# TB_Microcontroller.net
KiCad netlist of a schematic drawn in Altium Designer
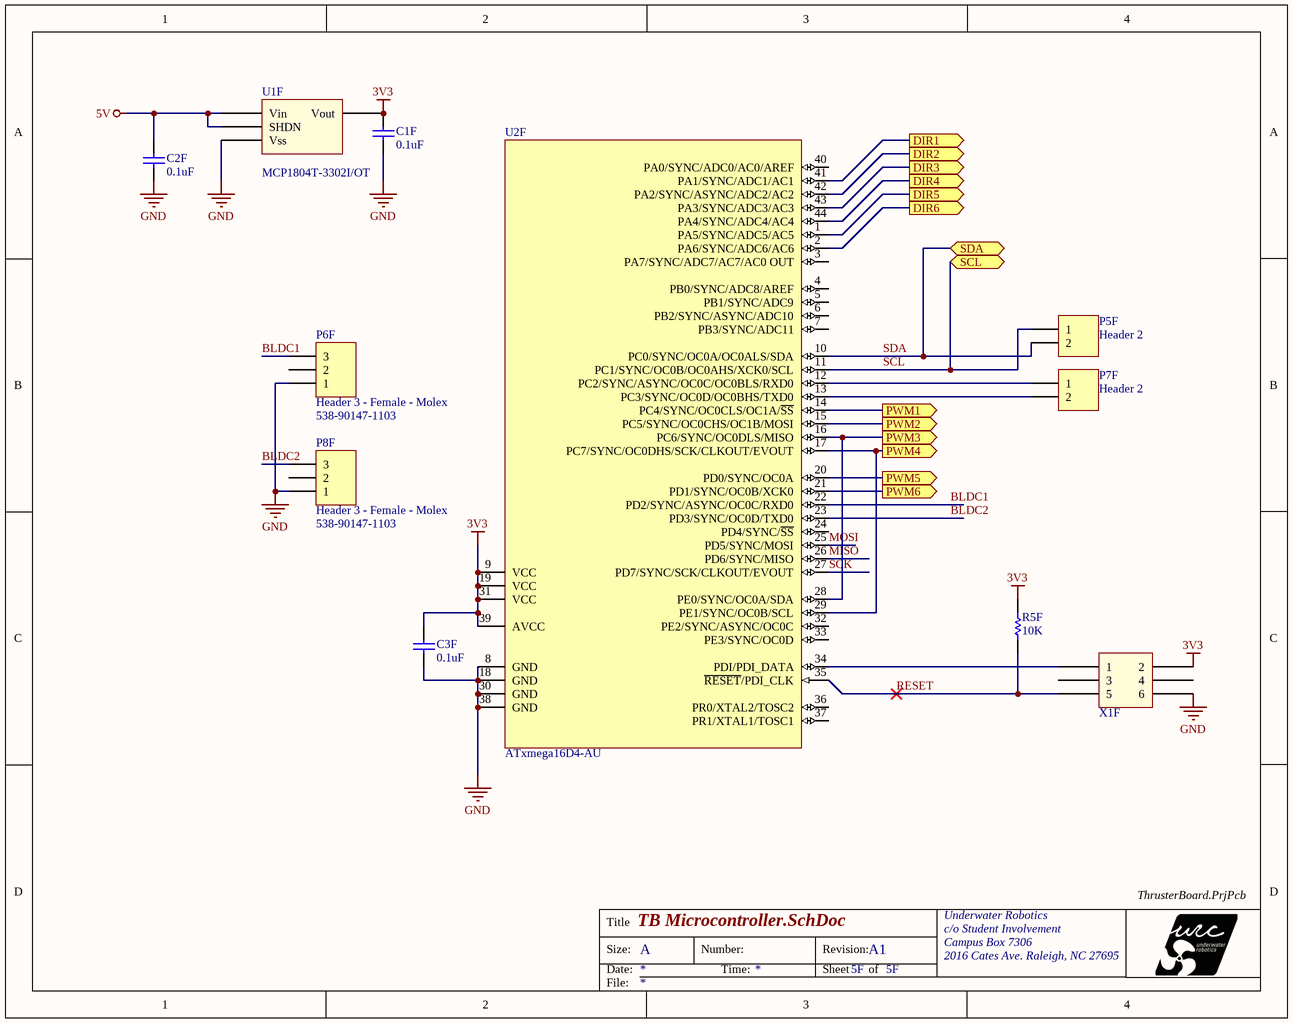
[diagram p0: TB Microcontroller.SchDoc]

(export (version "E")
  (design (tool "Eeschema 10.0.6"))
  (components
    (comp (ref "C1F")
      (value "0.1uF")
      (footprint "C0603")
      (description "Ceramic MLCC, Multicompo, X7R Dielectric")
      (fields
        (field (name "MANUFACTURER PART NUMBER") "MC0603B104K500CT")
        (field (name "Comment") "0.1uF, C0603, MultiComp")
      )
      (libsource (lib "Capacitors SchLib") (part "0.1uF, C0603, MultiComp"))
    )
    (comp (ref "C2F")
      (value "0.1uF")
      (footprint "C0603")
      (description "Ceramic MLCC, Multicompo, X7R Dielectric")
      (fields
        (field (name "MANUFACTURER PART NUMBER") "MC0603B104K500CT")
        (field (name "Comment") "0.1uF, C0603, MultiComp")
      )
      (libsource (lib "Capacitors SchLib") (part "0.1uF, C0603, MultiComp"))
    )
    (comp (ref "C3F")
      (value "0.1uF")
      (footprint "C0603")
      (description "Ceramic MLCC, Multicompo, X7R Dielectric")
      (fields
        (field (name "MANUFACTURER PART NUMBER") "MC0603B104K500CT")
        (field (name "Comment") "0.1uF, C0603, MultiComp")
      )
      (libsource (lib "Capacitors SchLib") (part "0.1uF, C0603, MultiComp"))
    )
    (comp (ref "P5F")
      (value "Header 2")
      (footprint "HDR1X2")
      (description "Header, 2-Pin")
      (fields (field (name "PUBLISHER") "Altium Limited"))
      (libsource (lib "Miscellaneous Connectors") (part "Header 2"))
    )
    (comp (ref "P6F")
      (value "Header 3 - Female - Molex")
      (footprint "HDR1X3 - Female - Molex")
      (description "Header, 3-Pin")
      (fields
        (field (name "MANUFACTURER") "Molex")
        (field (name "MANUFACTURER PART NUMBER") "90147-1103")
        (field (name "SUPPLIER PART NUMBER 1") "538-90147-1103")
      )
      (libsource (lib "URC_Lib") (part "Header 3 - Female - Molex"))
    )
    (comp (ref "P7F")
      (value "Header 2")
      (footprint "HDR1X2")
      (description "Header, 2-Pin")
      (fields (field (name "PUBLISHER") "Altium Limited"))
      (libsource (lib "Miscellaneous Connectors") (part "Header 2"))
    )
    (comp (ref "P8F")
      (value "Header 3 - Female - Molex")
      (footprint "HDR1X3 - Female - Molex")
      (description "Header, 3-Pin")
      (fields
        (field (name "MANUFACTURER") "Molex")
        (field (name "MANUFACTURER PART NUMBER") "90147-1103")
        (field (name "SUPPLIER PART NUMBER 1") "538-90147-1103")
      )
      (libsource (lib "URC_Lib") (part "Header 3 - Female - Molex"))
    )
    (comp (ref "R5F")
      (value "10K")
      (footprint "R0603")
      (description "Resistor")
      (fields (field (name "TOLERANCE") "1%") (field (name "MANUFACTURER PART NUMBER") "RC0603FR-1010KL"))
      (libsource (lib "Resistors SchLib") (part "10k, 1%, 100mW, Yageo, R0603"))
    )
    (comp (ref "U1F")
      (value "MCP1804T-3302I/OT")
      (footprint "MCP1804T-3302I/OT")
      (description "3.3V Linear Regulator")
      (fields (field (name "MANUFACTURER PART NUMBER") "MCP1804T-3302I/OT"))
      (libsource (lib "URC") (part "MCP1804T-3302I/OT"))
    )
    (comp (ref "U2F")
      (value "ATxmega16D4-AU")
      (footprint "44A_N")
      (fields (field (name "MANUFACTURER PART NUMBER") "ATXMEGA16D4-AU"))
      (libsource (lib "Atmel Microcontroller AVR XMEGA") (part "ATxmega16D4-AU"))
    )
    (comp (ref "X1F")
      (value "Header")
      (footprint "2x3 Header")
      (description "2x3 Header")
      (fields (field (name "MANUFACTURER PART NUMBER") "67996-406HLF"))
      (libsource (lib "URC") (part "2x3 Header"))
    )
  )
  (nets
    (net (code "1") (name "/BLDC1") (class "Default")
      (node (ref "P6F") (pin "3") (pinfunction "3_3") (pintype "passive"))
      (node (ref "U2F") (pin "22") (pinfunction "PD2/SYNC/ASYNC/OC0C/RXD0_22") (pintype "bidirectional"))
    )
    (net (code "2") (name "/BLDC2") (class "Default")
      (node (ref "P8F") (pin "3") (pinfunction "3_3") (pintype "passive"))
      (node (ref "U2F") (pin "23") (pinfunction "PD3/SYNC/OC0D/TXD0_23") (pintype "bidirectional"))
    )
    (net (code "3") (name "/DIR1") (class "Default")
      (node (ref "U2F") (pin "41") (pinfunction "PA1/SYNC/ADC1/AC1_41") (pintype "bidirectional"))
    )
    (net (code "4") (name "/DIR2") (class "Default")
      (node (ref "U2F") (pin "42") (pinfunction "PA2/SYNC/ASYNC/ADC2/AC2_42") (pintype "bidirectional"))
    )
    (net (code "5") (name "/DIR3") (class "Default")
      (node (ref "U2F") (pin "43") (pinfunction "PA3/SYNC/ADC3/AC3_43") (pintype "bidirectional"))
    )
    (net (code "6") (name "/DIR4") (class "Default")
      (node (ref "U2F") (pin "44") (pinfunction "PA4/SYNC/ADC4/AC4_44") (pintype "bidirectional"))
    )
    (net (code "7") (name "/DIR5") (class "Default")
      (node (ref "U2F") (pin "1") (pinfunction "PA5/SYNC/ADC5/AC5_1") (pintype "bidirectional"))
    )
    (net (code "8") (name "/DIR6") (class "Default")
      (node (ref "U2F") (pin "2") (pinfunction "PA6/SYNC/ADC6/AC6_2") (pintype "bidirectional"))
    )
    (net (code "9") (name "/MISO") (class "Default")
      (node (ref "U2F") (pin "26") (pinfunction "PD6/SYNC/MISO_26") (pintype "bidirectional"))
    )
    (net (code "10") (name "/MOSI") (class "Default")
      (node (ref "U2F") (pin "25") (pinfunction "PD5/SYNC/MOSI_25") (pintype "bidirectional"))
    )
    (net (code "11") (name "/PWM1") (class "Default")
      (node (ref "U2F") (pin "14") (pinfunction "PC4/SYNC/OC0CLS/OC1A/~{SS}_14") (pintype "bidirectional"))
    )
    (net (code "12") (name "/PWM2") (class "Default")
      (node (ref "U2F") (pin "15") (pinfunction "PC5/SYNC/OC0CHS/OC1B/MOSI_15") (pintype "bidirectional"))
    )
    (net (code "13") (name "/PWM3") (class "Default")
      (node (ref "U2F") (pin "16") (pinfunction "PC6/SYNC/OC0DLS/MISO_16") (pintype "bidirectional"))
      (node (ref "U2F") (pin "28") (pinfunction "PE0/SYNC/OC0A/SDA_28") (pintype "bidirectional"))
    )
    (net (code "14") (name "/PWM4") (class "Default")
      (node (ref "U2F") (pin "17") (pinfunction "PC7/SYNC/OC0DHS/SCK/CLKOUT/EVOUT_17") (pintype "bidirectional"))
      (node (ref "U2F") (pin "29") (pinfunction "PE1/SYNC/OC0B/SCL_29") (pintype "bidirectional"))
    )
    (net (code "15") (name "/PWM5") (class "Default")
      (node (ref "U2F") (pin "20") (pinfunction "PD0/SYNC/OC0A_20") (pintype "bidirectional"))
    )
    (net (code "16") (name "/PWM6") (class "Default")
      (node (ref "U2F") (pin "21") (pinfunction "PD1/SYNC/OC0B/XCK0_21") (pintype "bidirectional"))
    )
    (net (code "18") (name "/RESET") (class "Default")
      (node (ref "R5F") (pin "1") (pinfunction "1_1") (pintype "passive"))
      (node (ref "U2F") (pin "35") (pinfunction "~{RESET}/PDI_CLK_35") (pintype "input"))
      (node (ref "X1F") (pin "5") (pinfunction "5_5") (pintype "passive"))
    )
    (net (code "19") (name "/SCK") (class "Default")
      (node (ref "U2F") (pin "27") (pinfunction "PD7/SYNC/SCK/CLKOUT/EVOUT_27") (pintype "bidirectional"))
    )
    (net (code "20") (name "/SCL") (class "Default")
      (node (ref "P5F") (pin "1") (pinfunction "1_1") (pintype "passive"))
      (node (ref "U2F") (pin "11") (pinfunction "PC1/SYNC/OC0B/OC0AHS/XCK0/SCL_11") (pintype "bidirectional"))
    )
    (net (code "21") (name "/SDA") (class "Default")
      (node (ref "P5F") (pin "2") (pinfunction "2_2") (pintype "passive"))
      (node (ref "U2F") (pin "10") (pinfunction "PC0/SYNC/OC0A/OC0ALS/SDA_10") (pintype "bidirectional"))
    )
    (net (code "22") (name "3V3") (class "Default")
      (node (ref "C1F") (pin "1") (pinfunction "+_1") (pintype "passive"))
      (node (ref "C3F") (pin "1") (pinfunction "+_1") (pintype "passive"))
      (node (ref "R5F") (pin "2") (pinfunction "2_2") (pintype "passive"))
      (node (ref "U1F") (pin "Vout") (pinfunction "Vout_Vout") (pintype "passive"))
      (node (ref "U2F") (pin "19") (pinfunction "VCC_19") (pintype "power_in"))
      (node (ref "U2F") (pin "31") (pinfunction "VCC_31") (pintype "power_in"))
      (node (ref "U2F") (pin "39") (pinfunction "AVCC_39") (pintype "power_in"))
      (node (ref "U2F") (pin "9") (pinfunction "VCC_9") (pintype "power_in"))
      (node (ref "X1F") (pin "2") (pinfunction "2_2") (pintype "passive"))
    )
    (net (code "23") (name "5V") (class "Default")
      (node (ref "C2F") (pin "1") (pinfunction "+_1") (pintype "passive"))
      (node (ref "U1F") (pin "SHDN") (pinfunction "SHDN_SHDN") (pintype "passive"))
      (node (ref "U1F") (pin "Vin") (pinfunction "Vin_Vin") (pintype "passive"))
    )
    (net (code "24") (name "GND") (class "Default")
      (node (ref "C1F") (pin "2") (pinfunction "2_2") (pintype "passive"))
      (node (ref "C2F") (pin "2") (pinfunction "2_2") (pintype "passive"))
      (node (ref "C3F") (pin "2") (pinfunction "2_2") (pintype "passive"))
      (node (ref "P6F") (pin "1") (pinfunction "1_1") (pintype "passive"))
      (node (ref "P8F") (pin "1") (pinfunction "1_1") (pintype "passive"))
      (node (ref "U1F") (pin "Vss") (pinfunction "Vss_Vss") (pintype "passive"))
      (node (ref "U2F") (pin "18") (pinfunction "GND_18") (pintype "power_in"))
      (node (ref "U2F") (pin "30") (pinfunction "GND_30") (pintype "power_in"))
      (node (ref "U2F") (pin "38") (pinfunction "GND_38") (pintype "power_in"))
      (node (ref "U2F") (pin "8") (pinfunction "GND_8") (pintype "power_in"))
      (node (ref "X1F") (pin "6") (pinfunction "6_6") (pintype "passive"))
    )
    (net (code "25") (name "Net-(U2F-PC2{slash}SYNC{slash}ASYNC{slash}OC0C{slash}OC0BLS{slash}RXD0)") (class "Default")
      (node (ref "P7F") (pin "1") (pinfunction "1_1") (pintype "passive"))
      (node (ref "U2F") (pin "12") (pinfunction "PC2/SYNC/ASYNC/OC0C/OC0BLS/RXD0_12") (pintype "bidirectional"))
    )
    (net (code "26") (name "Net-(U2F-PC3{slash}SYNC{slash}OC0D{slash}OC0BHS{slash}TXD0)") (class "Default")
      (node (ref "P7F") (pin "2") (pinfunction "2_2") (pintype "passive"))
      (node (ref "U2F") (pin "13") (pinfunction "PC3/SYNC/OC0D/OC0BHS/TXD0_13") (pintype "bidirectional"))
    )
    (net (code "27") (name "Net-(U2F-PDI{slash}PDI_DATA)") (class "Default")
      (node (ref "U2F") (pin "34") (pinfunction "PDI/PDI_DATA_34") (pintype "bidirectional"))
      (node (ref "X1F") (pin "1") (pinfunction "1_1") (pintype "passive"))
    )
    (net (code "28") (name "unconnected-(P6F-Pad2)") (class "Default")
      (node (ref "P6F") (pin "2") (pinfunction "2_2") (pintype "passive"))
    )
    (net (code "29") (name "unconnected-(P8F-Pad2)") (class "Default")
      (node (ref "P8F") (pin "2") (pinfunction "2_2") (pintype "passive"))
    )
    (net (code "30") (name "unconnected-(U2F-PA0{slash}SYNC{slash}ADC0{slash}AC0{slash}AREF-Pad40)") (class "Default")
      (node (ref "U2F") (pin "40") (pinfunction "PA0/SYNC/ADC0/AC0/AREF_40") (pintype "bidirectional"))
    )
    (net (code "31") (name "unconnected-(U2F-PA7{slash}SYNC{slash}ADC7{slash}AC7{slash}AC0_OUT-Pad3)") (class "Default")
      (node (ref "U2F") (pin "3") (pinfunction "PA7/SYNC/ADC7/AC7/AC0_OUT_3") (pintype "bidirectional"))
    )
    (net (code "32") (name "unconnected-(U2F-PB0{slash}SYNC{slash}ADC8{slash}AREF-Pad4)") (class "Default")
      (node (ref "U2F") (pin "4") (pinfunction "PB0/SYNC/ADC8/AREF_4") (pintype "bidirectional"))
    )
    (net (code "33") (name "unconnected-(U2F-PB1{slash}SYNC{slash}ADC9-Pad5)") (class "Default")
      (node (ref "U2F") (pin "5") (pinfunction "PB1/SYNC/ADC9_5") (pintype "bidirectional"))
    )
    (net (code "34") (name "unconnected-(U2F-PB2{slash}SYNC{slash}ASYNC{slash}ADC10-Pad6)") (class "Default")
      (node (ref "U2F") (pin "6") (pinfunction "PB2/SYNC/ASYNC/ADC10_6") (pintype "bidirectional"))
    )
    (net (code "35") (name "unconnected-(U2F-PB3{slash}SYNC{slash}ADC11-Pad7)") (class "Default")
      (node (ref "U2F") (pin "7") (pinfunction "PB3/SYNC/ADC11_7") (pintype "bidirectional"))
    )
    (net (code "36") (name "unconnected-(U2F-PD4{slash}SYNC{slash}~{SS}-Pad24)") (class "Default")
      (node (ref "U2F") (pin "24") (pinfunction "PD4/SYNC/~{SS}_24") (pintype "bidirectional"))
    )
    (net (code "37") (name "unconnected-(U2F-PE2{slash}SYNC{slash}ASYNC{slash}OC0C-Pad32)") (class "Default")
      (node (ref "U2F") (pin "32") (pinfunction "PE2/SYNC/ASYNC/OC0C_32") (pintype "bidirectional"))
    )
    (net (code "38") (name "unconnected-(U2F-PE3{slash}SYNC{slash}OC0D-Pad33)") (class "Default")
      (node (ref "U2F") (pin "33") (pinfunction "PE3/SYNC/OC0D_33") (pintype "bidirectional"))
    )
    (net (code "39") (name "unconnected-(U2F-PR0{slash}XTAL2{slash}TOSC2-Pad36)") (class "Default")
      (node (ref "U2F") (pin "36") (pinfunction "PR0/XTAL2/TOSC2_36") (pintype "bidirectional"))
    )
    (net (code "40") (name "unconnected-(U2F-PR1{slash}XTAL1{slash}TOSC1-Pad37)") (class "Default")
      (node (ref "U2F") (pin "37") (pinfunction "PR1/XTAL1/TOSC1_37") (pintype "bidirectional"))
    )
    (net (code "41") (name "unconnected-(X1F-Pad3)") (class "Default")
      (node (ref "X1F") (pin "3") (pinfunction "3_3") (pintype "passive"))
    )
    (net (code "42") (name "unconnected-(X1F-Pad4)") (class "Default")
      (node (ref "X1F") (pin "4") (pinfunction "4_4") (pintype "passive"))
    )
  )
)
